# USB_Multiplicator.net
KiCad netlist of a schematic drawn in EAGLE
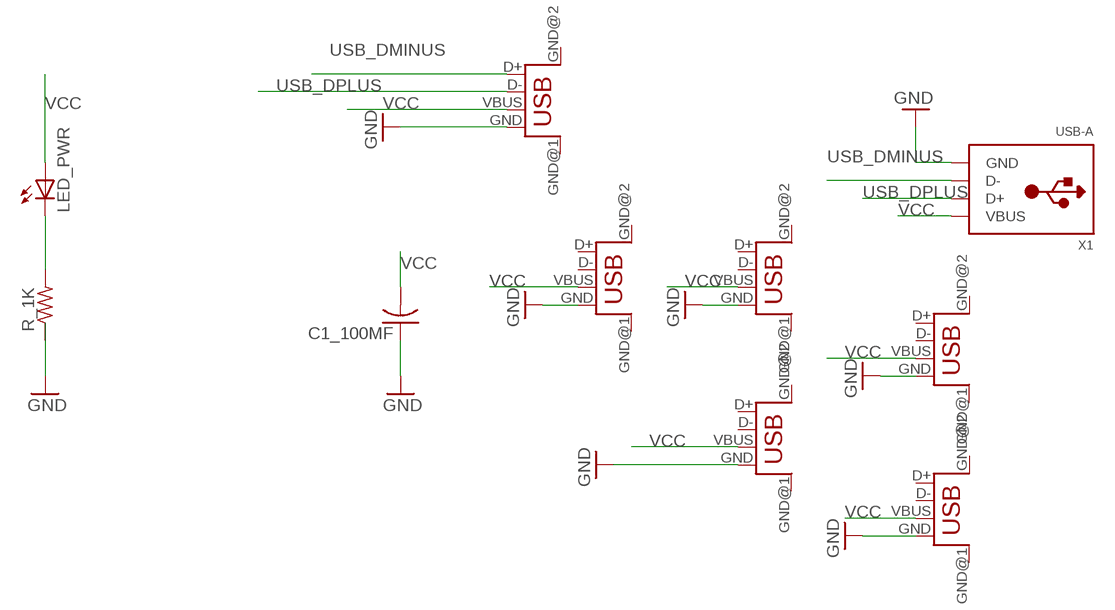
[diagram p0: schematic, sheet 1]

(export (version "E")
  (design (tool "Eeschema 10.0.6"))
  (components
    (comp (ref "C1_100MF")
      (value "C-US025-030X050")
      (footprint "eagle-import:C025-030X050")
      (libsource (lib "eagle-import") (part "C-US025-030X050"))
    )
    (comp (ref "LED_PWR")
      (value "LEDSMT1206")
      (footprint "eagle-import:1206")
      (libsource (lib "eagle-import") (part "LEDSMT1206"))
    )
    (comp (ref "R_1K")
      (value "R-US_R1206")
      (footprint "eagle-import:R1206")
      (libsource (lib "eagle-import") (part "R-US_R1206"))
    )
    (comp (ref "USB_OUT_2")
      (value "USB")
      (footprint "eagle-import:USB-FEMALE-A-PTH")
      (libsource (lib "eagle-import") (part "USB"))
    )
    (comp (ref "USB_OUT_3")
      (value "USB")
      (footprint "eagle-import:USB-FEMALE-A-PTH")
      (libsource (lib "eagle-import") (part "USB"))
    )
    (comp (ref "USB_OUT_4")
      (value "USB")
      (footprint "eagle-import:USB-FEMALE-A-PTH")
      (libsource (lib "eagle-import") (part "USB"))
    )
    (comp (ref "USB_OUT_5")
      (value "USB")
      (footprint "eagle-import:USB-FEMALE-A-PTH")
      (libsource (lib "eagle-import") (part "USB"))
    )
    (comp (ref "USB_OUT_6")
      (value "USB")
      (footprint "eagle-import:USB-FEMALE-A-PTH")
      (libsource (lib "eagle-import") (part "USB"))
    )
    (comp (ref "USB_OUT_WITH_DATA_1")
      (value "USB")
      (footprint "eagle-import:USB-FEMALE-A-PTH")
      (libsource (lib "eagle-import") (part "USB"))
    )
    (comp (ref "X1")
      (value "USB-A")
      (footprint "eagle-import:MOLEX_480371000")
      (libsource (lib "eagle-import") (part "USB-A"))
    )
  )
  (nets
    (net (code "1") (name "/USB_DMINUS") (class "Default")
      (node (ref "USB_OUT_WITH_DATA_1") (pin "D+") (pinfunction "D+_D+") (pintype "bidirectional"))
      (node (ref "X1") (pin "2") (pinfunction "D-_2") (pintype "bidirectional"))
    )
    (net (code "2") (name "/USB_DPLUS") (class "Default")
      (node (ref "USB_OUT_WITH_DATA_1") (pin "D-") (pinfunction "D-_D-") (pintype "bidirectional"))
      (node (ref "X1") (pin "3") (pinfunction "D+_3") (pintype "bidirectional"))
    )
    (net (code "3") (name "/VCC") (class "Default")
      (node (ref "C1_100MF") (pin "2") (pinfunction "2_2") (pintype "passive"))
      (node (ref "LED_PWR") (pin "A") (pinfunction "A_A") (pintype "passive"))
      (node (ref "USB_OUT_2") (pin "VBUS") (pinfunction "VBUS_VBUS") (pintype "bidirectional"))
      (node (ref "USB_OUT_3") (pin "VBUS") (pinfunction "VBUS_VBUS") (pintype "bidirectional"))
      (node (ref "USB_OUT_4") (pin "VBUS") (pinfunction "VBUS_VBUS") (pintype "bidirectional"))
      (node (ref "USB_OUT_5") (pin "VBUS") (pinfunction "VBUS_VBUS") (pintype "bidirectional"))
      (node (ref "USB_OUT_6") (pin "VBUS") (pinfunction "VBUS_VBUS") (pintype "bidirectional"))
      (node (ref "USB_OUT_WITH_DATA_1") (pin "VBUS") (pinfunction "VBUS_VBUS") (pintype "bidirectional"))
      (node (ref "X1") (pin "1") (pinfunction "VBUS_1") (pintype "power_in"))
    )
    (net (code "4") (name "GND") (class "Default")
      (node (ref "C1_100MF") (pin "1") (pinfunction "1_1") (pintype "passive"))
      (node (ref "R_1K") (pin "1") (pinfunction "1_1") (pintype "passive"))
      (node (ref "USB_OUT_2") (pin "GND") (pinfunction "GND_GND") (pintype "bidirectional"))
      (node (ref "USB_OUT_3") (pin "GND") (pinfunction "GND_GND") (pintype "bidirectional"))
      (node (ref "USB_OUT_4") (pin "GND") (pinfunction "GND_GND") (pintype "bidirectional"))
      (node (ref "USB_OUT_5") (pin "GND") (pinfunction "GND_GND") (pintype "bidirectional"))
      (node (ref "USB_OUT_6") (pin "GND") (pinfunction "GND_GND") (pintype "bidirectional"))
      (node (ref "USB_OUT_WITH_DATA_1") (pin "GND") (pinfunction "GND_GND") (pintype "bidirectional"))
      (node (ref "X1") (pin "4") (pinfunction "GND_4") (pintype "power_in"))
    )
    (net (code "5") (name "Net-(LED_PWR-PadC)") (class "Default")
      (node (ref "LED_PWR") (pin "C") (pinfunction "C_C") (pintype "passive"))
      (node (ref "R_1K") (pin "2") (pinfunction "2_2") (pintype "passive"))
    )
    (net (code "6") (name "unconnected-(USB_OUT_2-GND-PadGND@1)") (class "Default")
      (node (ref "USB_OUT_2") (pin "GND@1") (pinfunction "GND_GND@1") (pintype "bidirectional"))
    )
    (net (code "7") (name "unconnected-(USB_OUT_2-GND-PadGND@2)") (class "Default")
      (node (ref "USB_OUT_2") (pin "GND@2") (pinfunction "GND_GND@2") (pintype "bidirectional"))
    )
    (net (code "8") (name "unconnected-(USB_OUT_2-PadD+)") (class "Default")
      (node (ref "USB_OUT_2") (pin "D+") (pinfunction "D+_D+") (pintype "bidirectional"))
    )
    (net (code "9") (name "unconnected-(USB_OUT_2-PadD-)") (class "Default")
      (node (ref "USB_OUT_2") (pin "D-") (pinfunction "D-_D-") (pintype "bidirectional"))
    )
    (net (code "10") (name "unconnected-(USB_OUT_3-GND-PadGND@1)") (class "Default")
      (node (ref "USB_OUT_3") (pin "GND@1") (pinfunction "GND_GND@1") (pintype "bidirectional"))
    )
    (net (code "11") (name "unconnected-(USB_OUT_3-GND-PadGND@2)") (class "Default")
      (node (ref "USB_OUT_3") (pin "GND@2") (pinfunction "GND_GND@2") (pintype "bidirectional"))
    )
    (net (code "12") (name "unconnected-(USB_OUT_3-PadD+)") (class "Default")
      (node (ref "USB_OUT_3") (pin "D+") (pinfunction "D+_D+") (pintype "bidirectional"))
    )
    (net (code "13") (name "unconnected-(USB_OUT_3-PadD-)") (class "Default")
      (node (ref "USB_OUT_3") (pin "D-") (pinfunction "D-_D-") (pintype "bidirectional"))
    )
    (net (code "14") (name "unconnected-(USB_OUT_4-GND-PadGND@1)") (class "Default")
      (node (ref "USB_OUT_4") (pin "GND@1") (pinfunction "GND_GND@1") (pintype "bidirectional"))
    )
    (net (code "15") (name "unconnected-(USB_OUT_4-GND-PadGND@2)") (class "Default")
      (node (ref "USB_OUT_4") (pin "GND@2") (pinfunction "GND_GND@2") (pintype "bidirectional"))
    )
    (net (code "16") (name "unconnected-(USB_OUT_4-PadD+)") (class "Default")
      (node (ref "USB_OUT_4") (pin "D+") (pinfunction "D+_D+") (pintype "bidirectional"))
    )
    (net (code "17") (name "unconnected-(USB_OUT_4-PadD-)") (class "Default")
      (node (ref "USB_OUT_4") (pin "D-") (pinfunction "D-_D-") (pintype "bidirectional"))
    )
    (net (code "18") (name "unconnected-(USB_OUT_5-GND-PadGND@1)") (class "Default")
      (node (ref "USB_OUT_5") (pin "GND@1") (pinfunction "GND_GND@1") (pintype "bidirectional"))
    )
    (net (code "19") (name "unconnected-(USB_OUT_5-GND-PadGND@2)") (class "Default")
      (node (ref "USB_OUT_5") (pin "GND@2") (pinfunction "GND_GND@2") (pintype "bidirectional"))
    )
    (net (code "20") (name "unconnected-(USB_OUT_5-PadD+)") (class "Default")
      (node (ref "USB_OUT_5") (pin "D+") (pinfunction "D+_D+") (pintype "bidirectional"))
    )
    (net (code "21") (name "unconnected-(USB_OUT_5-PadD-)") (class "Default")
      (node (ref "USB_OUT_5") (pin "D-") (pinfunction "D-_D-") (pintype "bidirectional"))
    )
    (net (code "22") (name "unconnected-(USB_OUT_6-GND-PadGND@1)") (class "Default")
      (node (ref "USB_OUT_6") (pin "GND@1") (pinfunction "GND_GND@1") (pintype "bidirectional"))
    )
    (net (code "23") (name "unconnected-(USB_OUT_6-GND-PadGND@2)") (class "Default")
      (node (ref "USB_OUT_6") (pin "GND@2") (pinfunction "GND_GND@2") (pintype "bidirectional"))
    )
    (net (code "24") (name "unconnected-(USB_OUT_6-PadD+)") (class "Default")
      (node (ref "USB_OUT_6") (pin "D+") (pinfunction "D+_D+") (pintype "bidirectional"))
    )
    (net (code "25") (name "unconnected-(USB_OUT_6-PadD-)") (class "Default")
      (node (ref "USB_OUT_6") (pin "D-") (pinfunction "D-_D-") (pintype "bidirectional"))
    )
    (net (code "26") (name "unconnected-(USB_OUT_WITH_DATA_1-GND-PadGND@1)") (class "Default")
      (node (ref "USB_OUT_WITH_DATA_1") (pin "GND@1") (pinfunction "GND_GND@1") (pintype "bidirectional"))
    )
    (net (code "27") (name "unconnected-(USB_OUT_WITH_DATA_1-GND-PadGND@2)") (class "Default")
      (node (ref "USB_OUT_WITH_DATA_1") (pin "GND@2") (pinfunction "GND_GND@2") (pintype "bidirectional"))
    )
  )
)
